# rpi_exp_can.net
KiCad netlist of a schematic drawn in EAGLE
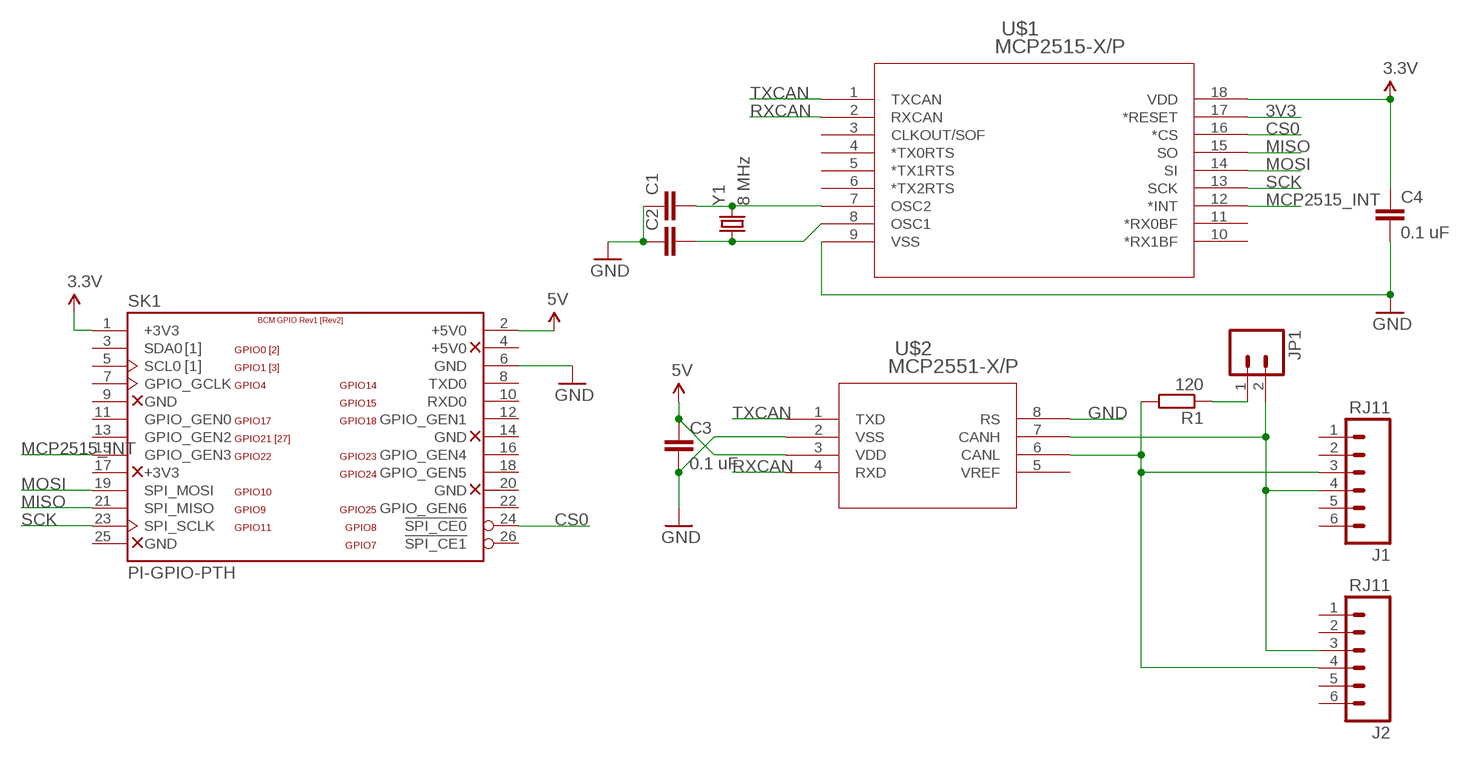
[diagram p0: schematic, sheet 1]

(export (version "E")
  (design (tool "Eeschema 10.0.6"))
  (components
    (comp (ref "C1")
      (value "C-EU025-025X050")
      (footprint "eagle-import:C025-025X050")
      (libsource (lib "eagle-import") (part "C-EU025-025X050"))
    )
    (comp (ref "C2")
      (value "C-EU025-025X050")
      (footprint "eagle-import:C025-025X050")
      (libsource (lib "eagle-import") (part "C-EU025-025X050"))
    )
    (comp (ref "C3")
      (value "0.1 uF")
      (footprint "eagle-import:C050-030X075")
      (libsource (lib "eagle-import") (part "C-EU050-030X075"))
    )
    (comp (ref "C4")
      (value "0.1 uF")
      (footprint "eagle-import:C050-030X075")
      (libsource (lib "eagle-import") (part "C-EU050-030X075"))
    )
    (comp (ref "J1")
      (value "RJ11")
      (footprint "eagle-import:RJ11-6")
      (libsource (lib "eagle-import") (part "RJ11-6PTH"))
    )
    (comp (ref "J2")
      (value "RJ11")
      (footprint "eagle-import:RJ11-6")
      (libsource (lib "eagle-import") (part "RJ11-6PTH"))
    )
    (comp (ref "JP1")
      (value "M02PTH")
      (footprint "eagle-import:1X02")
      (libsource (lib "eagle-import") (part "M02PTH"))
    )
    (comp (ref "R1")
      (value "120")
      (footprint "eagle-import:0207_10")
      (libsource (lib "eagle-import") (part "R-EU_0207/10"))
    )
    (comp (ref "SK1")
      (value "PI-GPIO-PTH")
      (footprint "eagle-import:GPIO-CONNECTOR")
      (libsource (lib "eagle-import") (part "PI-GPIO-PTH"))
    )
    (comp (ref "U$1")
      (value "MCP2515-X/P")
      (footprint "eagle-import:PDIP18_300MC")
      (libsource (lib "eagle-import") (part "MCP2515-X/P"))
    )
    (comp (ref "U$2")
      (value "MCP2551-X/P")
      (footprint "eagle-import:PDIP8_300MC")
      (libsource (lib "eagle-import") (part "MCP2551-X/P"))
    )
    (comp (ref "Y1")
      (value "8 MHz")
      (footprint "eagle-import:HC49US")
      (libsource (lib "eagle-import") (part "CRYSTALHC49US"))
    )
  )
  (nets
    (net (code "1") (name "/3V3") (class "Default")
      (node (ref "U$1") (pin "17") (pinfunction "*RESET_17") (pintype "passive"))
    )
    (net (code "2") (name "/CS0") (class "Default")
      (node (ref "SK1") (pin "24") (pinfunction "~{SPI_CE0}_24") (pintype "bidirectional"))
      (node (ref "U$1") (pin "16") (pinfunction "*CS_16") (pintype "passive"))
    )
    (net (code "3") (name "/MCP2515_INT") (class "Default")
      (node (ref "SK1") (pin "15") (pinfunction "GPIO_GEN3_15") (pintype "bidirectional"))
      (node (ref "U$1") (pin "12") (pinfunction "*INT_12") (pintype "passive"))
    )
    (net (code "4") (name "/MISO") (class "Default")
      (node (ref "SK1") (pin "21") (pinfunction "SPI_MISO_21") (pintype "bidirectional"))
      (node (ref "U$1") (pin "15") (pinfunction "SO_15") (pintype "passive"))
    )
    (net (code "5") (name "/MOSI") (class "Default")
      (node (ref "SK1") (pin "19") (pinfunction "SPI_MOSI_19") (pintype "bidirectional"))
      (node (ref "U$1") (pin "14") (pinfunction "SI_14") (pintype "passive"))
    )
    (net (code "6") (name "/RXCAN") (class "Default")
      (node (ref "U$1") (pin "2") (pinfunction "RXCAN_2") (pintype "passive"))
      (node (ref "U$2") (pin "4") (pinfunction "RXD_4") (pintype "passive"))
    )
    (net (code "7") (name "/SCK") (class "Default")
      (node (ref "SK1") (pin "23") (pinfunction "SPI_SCLK_23") (pintype "bidirectional"))
      (node (ref "U$1") (pin "13") (pinfunction "SCK_13") (pintype "passive"))
    )
    (net (code "8") (name "/TXCAN") (class "Default")
      (node (ref "U$1") (pin "1") (pinfunction "TXCAN_1") (pintype "passive"))
      (node (ref "U$2") (pin "1") (pinfunction "TXD_1") (pintype "passive"))
    )
    (net (code "9") (name "3.3V") (class "Default")
      (node (ref "C4") (pin "1") (pinfunction "1_1") (pintype "passive"))
      (node (ref "SK1") (pin "1") (pinfunction "+3V3_1") (pintype "power_in"))
      (node (ref "U$1") (pin "18") (pinfunction "VDD_18") (pintype "passive"))
    )
    (net (code "10") (name "5V") (class "Default")
      (node (ref "C3") (pin "1") (pinfunction "1_1") (pintype "passive"))
      (node (ref "SK1") (pin "2") (pinfunction "+5V0_2") (pintype "power_in"))
      (node (ref "U$2") (pin "3") (pinfunction "VDD_3") (pintype "passive"))
    )
    (net (code "11") (name "GND") (class "Default")
      (node (ref "C1") (pin "1") (pinfunction "1_1") (pintype "passive"))
      (node (ref "C2") (pin "1") (pinfunction "1_1") (pintype "passive"))
      (node (ref "C3") (pin "2") (pinfunction "2_2") (pintype "passive"))
      (node (ref "C4") (pin "2") (pinfunction "2_2") (pintype "passive"))
      (node (ref "SK1") (pin "6") (pinfunction "GND_6") (pintype "power_in"))
      (node (ref "U$1") (pin "9") (pinfunction "VSS_9") (pintype "passive"))
      (node (ref "U$2") (pin "2") (pinfunction "VSS_2") (pintype "passive"))
      (node (ref "U$2") (pin "8") (pinfunction "RS_8") (pintype "passive"))
    )
    (net (code "12") (name "Net-(JP1-Pad1)") (class "Default")
      (node (ref "JP1") (pin "1") (pinfunction "1_1") (pintype "passive"))
      (node (ref "R1") (pin "1") (pinfunction "1_1") (pintype "passive"))
    )
    (net (code "13") (name "Net-(U$1-OSC1)") (class "Default")
      (node (ref "C2") (pin "2") (pinfunction "2_2") (pintype "passive"))
      (node (ref "U$1") (pin "8") (pinfunction "OSC1_8") (pintype "passive"))
      (node (ref "Y1") (pin "1") (pinfunction "1_1") (pintype "passive"))
    )
    (net (code "14") (name "Net-(U$1-OSC2)") (class "Default")
      (node (ref "C1") (pin "2") (pinfunction "2_2") (pintype "passive"))
      (node (ref "U$1") (pin "7") (pinfunction "OSC2_7") (pintype "passive"))
      (node (ref "Y1") (pin "2") (pinfunction "2_2") (pintype "passive"))
    )
    (net (code "15") (name "Net-(U$2-CANH)") (class "Default")
      (node (ref "J1") (pin "4") (pinfunction "4_4") (pintype "passive"))
      (node (ref "J2") (pin "3") (pinfunction "3_3") (pintype "passive"))
      (node (ref "JP1") (pin "2") (pinfunction "2_2") (pintype "passive"))
      (node (ref "U$2") (pin "7") (pinfunction "CANH_7") (pintype "passive"))
    )
    (net (code "16") (name "Net-(U$2-CANL)") (class "Default")
      (node (ref "J1") (pin "3") (pinfunction "3_3") (pintype "passive"))
      (node (ref "J2") (pin "4") (pinfunction "4_4") (pintype "passive"))
      (node (ref "R1") (pin "2") (pinfunction "2_2") (pintype "passive"))
      (node (ref "U$2") (pin "6") (pinfunction "CANL_6") (pintype "passive"))
    )
    (net (code "17") (name "unconnected-(J1-Pad1)") (class "Default")
      (node (ref "J1") (pin "1") (pinfunction "1_1") (pintype "passive"))
    )
    (net (code "18") (name "unconnected-(J1-Pad2)") (class "Default")
      (node (ref "J1") (pin "2") (pinfunction "2_2") (pintype "passive"))
    )
    (net (code "19") (name "unconnected-(J1-Pad5)") (class "Default")
      (node (ref "J1") (pin "5") (pinfunction "5_5") (pintype "passive"))
    )
    (net (code "20") (name "unconnected-(J1-Pad6)") (class "Default")
      (node (ref "J1") (pin "6") (pinfunction "6_6") (pintype "passive"))
    )
    (net (code "21") (name "unconnected-(J2-Pad1)") (class "Default")
      (node (ref "J2") (pin "1") (pinfunction "1_1") (pintype "passive"))
    )
    (net (code "22") (name "unconnected-(J2-Pad2)") (class "Default")
      (node (ref "J2") (pin "2") (pinfunction "2_2") (pintype "passive"))
    )
    (net (code "23") (name "unconnected-(J2-Pad5)") (class "Default")
      (node (ref "J2") (pin "5") (pinfunction "5_5") (pintype "passive"))
    )
    (net (code "24") (name "unconnected-(J2-Pad6)") (class "Default")
      (node (ref "J2") (pin "6") (pinfunction "6_6") (pintype "passive"))
    )
    (net (code "25") (name "unconnected-(SK1-+3V3-Pad17)") (class "Default")
      (node (ref "SK1") (pin "17") (pinfunction "+3V3_17") (pintype "no_connect"))
    )
    (net (code "26") (name "unconnected-(SK1-+5V0-Pad4)") (class "Default")
      (node (ref "SK1") (pin "4") (pinfunction "+5V0_4") (pintype "no_connect"))
    )
    (net (code "27") (name "unconnected-(SK1-GND-Pad9)") (class "Default")
      (node (ref "SK1") (pin "9") (pinfunction "GND_9") (pintype "no_connect"))
    )
    (net (code "28") (name "unconnected-(SK1-GND-Pad14)") (class "Default")
      (node (ref "SK1") (pin "14") (pinfunction "GND_14") (pintype "no_connect"))
    )
    (net (code "29") (name "unconnected-(SK1-GND-Pad20)") (class "Default")
      (node (ref "SK1") (pin "20") (pinfunction "GND_20") (pintype "no_connect"))
    )
    (net (code "30") (name "unconnected-(SK1-GND-Pad25)") (class "Default")
      (node (ref "SK1") (pin "25") (pinfunction "GND_25") (pintype "no_connect"))
    )
    (net (code "31") (name "unconnected-(SK1-GPIO_GCLK-Pad7)") (class "Default")
      (node (ref "SK1") (pin "7") (pinfunction "GPIO_GCLK_7") (pintype "bidirectional"))
    )
    (net (code "32") (name "unconnected-(SK1-GPIO_GEN0-Pad11)") (class "Default")
      (node (ref "SK1") (pin "11") (pinfunction "GPIO_GEN0_11") (pintype "bidirectional"))
    )
    (net (code "33") (name "unconnected-(SK1-GPIO_GEN1-Pad12)") (class "Default")
      (node (ref "SK1") (pin "12") (pinfunction "GPIO_GEN1_12") (pintype "bidirectional"))
    )
    (net (code "34") (name "unconnected-(SK1-GPIO_GEN2-Pad13)") (class "Default")
      (node (ref "SK1") (pin "13") (pinfunction "GPIO_GEN2_13") (pintype "bidirectional"))
    )
    (net (code "35") (name "unconnected-(SK1-GPIO_GEN4-Pad16)") (class "Default")
      (node (ref "SK1") (pin "16") (pinfunction "GPIO_GEN4_16") (pintype "bidirectional"))
    )
    (net (code "36") (name "unconnected-(SK1-GPIO_GEN5-Pad18)") (class "Default")
      (node (ref "SK1") (pin "18") (pinfunction "GPIO_GEN5_18") (pintype "bidirectional"))
    )
    (net (code "37") (name "unconnected-(SK1-GPIO_GEN6-Pad22)") (class "Default")
      (node (ref "SK1") (pin "22") (pinfunction "GPIO_GEN6_22") (pintype "bidirectional"))
    )
    (net (code "38") (name "unconnected-(SK1-RXD0-Pad10)") (class "Default")
      (node (ref "SK1") (pin "10") (pinfunction "RXD0_10") (pintype "bidirectional"))
    )
    (net (code "39") (name "unconnected-(SK1-SCL0-Pad5)") (class "Default")
      (node (ref "SK1") (pin "5") (pinfunction "SCL0_5") (pintype "bidirectional"))
    )
    (net (code "40") (name "unconnected-(SK1-SDA0-Pad3)") (class "Default")
      (node (ref "SK1") (pin "3") (pinfunction "SDA0_3") (pintype "bidirectional"))
    )
    (net (code "41") (name "unconnected-(SK1-TXD0-Pad8)") (class "Default")
      (node (ref "SK1") (pin "8") (pinfunction "TXD0_8") (pintype "bidirectional"))
    )
    (net (code "42") (name "unconnected-(SK1-~{SPI_CE1}-Pad26)") (class "Default")
      (node (ref "SK1") (pin "26") (pinfunction "~{SPI_CE1}_26") (pintype "bidirectional"))
    )
    (net (code "43") (name "unconnected-(U$1-*RX0BF-Pad11)") (class "Default")
      (node (ref "U$1") (pin "11") (pinfunction "*RX0BF_11") (pintype "passive"))
    )
    (net (code "44") (name "unconnected-(U$1-*RX1BF-Pad10)") (class "Default")
      (node (ref "U$1") (pin "10") (pinfunction "*RX1BF_10") (pintype "passive"))
    )
    (net (code "45") (name "unconnected-(U$1-*TX0RTS-Pad4)") (class "Default")
      (node (ref "U$1") (pin "4") (pinfunction "*TX0RTS_4") (pintype "passive"))
    )
    (net (code "46") (name "unconnected-(U$1-*TX1RTS-Pad5)") (class "Default")
      (node (ref "U$1") (pin "5") (pinfunction "*TX1RTS_5") (pintype "passive"))
    )
    (net (code "47") (name "unconnected-(U$1-*TX2RTS-Pad6)") (class "Default")
      (node (ref "U$1") (pin "6") (pinfunction "*TX2RTS_6") (pintype "passive"))
    )
    (net (code "48") (name "unconnected-(U$1-CLKOUT{slash}SOF-Pad3)") (class "Default")
      (node (ref "U$1") (pin "3") (pinfunction "CLKOUT/SOF_3") (pintype "passive"))
    )
    (net (code "49") (name "unconnected-(U$2-VREF-Pad5)") (class "Default")
      (node (ref "U$2") (pin "5") (pinfunction "VREF_5") (pintype "passive"))
    )
  )
)
